# RS485.net
KiCad netlist of a schematic drawn in Altium Designer
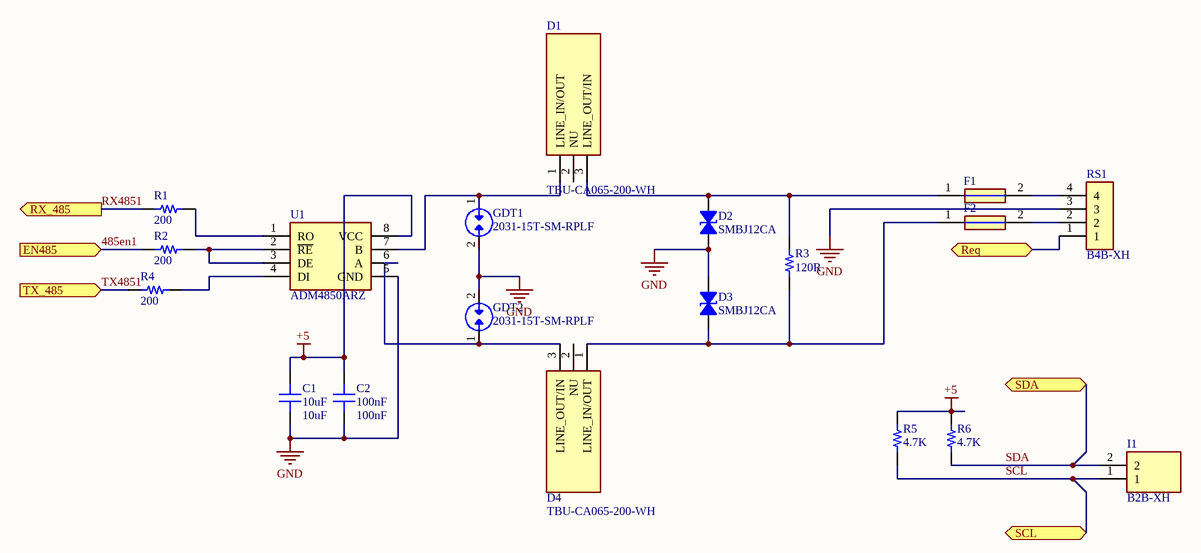
[diagram p0: RS485.SchDoc]

(export (version "E")
  (design (tool "Eeschema 10.0.6"))
  (components
    (comp (ref "C1")
      (value "10uF")
      (footprint "cap805")
      (description "CAP SMD 0805")
      (fields (field (name "PART NUMBER") "C0805X106K9RAC7800") (field (name "ALTIUM_VALUE") "10uF"))
      (libsource (lib "lamp control-ver2") (part "Capacitor"))
    )
    (comp (ref "C2")
      (value "100nF")
      (footprint "cap805")
      (description "CAP SMD 0805")
      (fields (field (name "PART NUMBER") "C0805X106K9RAC7800") (field (name "ALTIUM_VALUE") "100nF"))
      (libsource (lib "lamp control-ver2") (part "Capacitor"))
    )
    (comp (ref "D1")
      (value "TBU-CA065-200-WH")
      (footprint "TBUCA025050WH")
      (description "TVS Diode (Bi-directional)")
      (fields (field (name "MOUSER PART NUMBER") "652-TBU-CA065-200-WH"))
      (libsource (lib "*") (part "TBU-CA065-200-WH"))
    )
    (comp (ref "D2")
      (value "SMBJ12CA")
      (footprint "DO214AA SMB")
      (description "TVS DIODE 12V 19.9V SMB")
      (fields (field (name "MANUFACTURER") "AVX Corporation"))
      (libsource (lib "Celestial Altium Library - altium_library") (part "Diode TVS"))
    )
    (comp (ref "D3")
      (value "SMBJ12CA")
      (footprint "DO214AA SMB")
      (description "TVS DIODE 12V 19.9V SMB")
      (fields (field (name "MANUFACTURER") "AVX Corporation"))
      (libsource (lib "Celestial Altium Library - altium_library") (part "Diode TVS"))
    )
    (comp (ref "D4")
      (value "TBU-CA065-200-WH")
      (footprint "TBUCA025050WH")
      (description "TVS Diode (Bi-directional)")
      (fields (field (name "MOUSER PART NUMBER") "652-TBU-CA065-200-WH"))
      (libsource (lib "") (part "TBU-CA065-200-WH_1"))
    )
    (comp (ref "F1")
      (value "fuse 100mAmp")
      (footprint "fuse3216")
      (description "Fuse 1206")
      (fields (field (name "MANUFACTURER_PART_NUMBER") "1206SFS200F/63-2"))
      (libsource (lib "*") (part "1206SFS200F_63-2"))
    )
    (comp (ref "F2")
      (value "fuse 100mAmp")
      (footprint "fuse3216")
      (description "Fuse 1206")
      (fields (field (name "MANUFACTURER_PART_NUMBER") "1206SFS200F/63-2"))
      (libsource (lib "*") (part "1206SFS200F_63-2"))
    )
    (comp (ref "GDT1")
      (value "2031-15T-SM-RPLF")
      (footprint "TVS_2031-15T-SM-RPLF")
      (description "Gas Discharge Tube SMD")
      (libsource (lib "2031-15T-SM-RPLF") (part "2031-15T-SM-RPLF"))
    )
    (comp (ref "GDT2")
      (value "2031-15T-SM-RPLF")
      (footprint "TVS_2031-15T-SM-RPLF")
      (description "Gas Discharge Tube SMD")
      (libsource (lib "2031-15T-SM-RPLF") (part "2031-15T-SM-RPLF"))
    )
    (comp (ref "I1")
      (value "B2B-XH")
      (footprint "JST-B2B-XH")
      (description "XH 2pin standing")
      (libsource (lib "XHBBLIB") (part "B2B-XH"))
    )
    (comp (ref "R1")
      (value "200")
      (footprint "0603R")
      (description "RES SMD 0603")
      (fields (field (name "PART NUMBER") "CRCW080510K0JNEAIF") (field (name "MANUFACTURER") "Vishay Dale"))
      (libsource (lib "Celestial Altium Library - altium_library") (part "Resistor"))
    )
    (comp (ref "R2")
      (value "200")
      (footprint "0603R")
      (description "RES SMD 0603")
      (fields (field (name "PART NUMBER") "CRCW080510K0JNEAIF") (field (name "MANUFACTURER") "Vishay Dale"))
      (libsource (lib "Celestial Altium Library - altium_library") (part "Resistor"))
    )
    (comp (ref "R3")
      (value "120R")
      (footprint "0603R")
      (description "RES SMD 0603")
      (fields (field (name "PART NUMBER") "CRCW080510K0JNEAIF") (field (name "MANUFACTURER") "Vishay Dale"))
      (libsource (lib "Celestial Altium Library - altium_library") (part "Resistor"))
    )
    (comp (ref "R4")
      (value "200")
      (footprint "0603R")
      (description "RES SMD 0603")
      (fields (field (name "PART NUMBER") "CRCW080510K0JNEAIF") (field (name "MANUFACTURER") "Vishay Dale"))
      (libsource (lib "Celestial Altium Library - altium_library") (part "Resistor"))
    )
    (comp (ref "R5")
      (value "4.7K")
      (footprint "0603R")
      (description "RES SMD 0603")
      (fields (field (name "PART NUMBER") "CRCW080510K0JNEAIF") (field (name "MANUFACTURER") "Vishay Dale"))
      (libsource (lib "Celestial Altium Library - altium_library") (part "Resistor"))
    )
    (comp (ref "R6")
      (value "4.7K")
      (footprint "0603R")
      (description "RES SMD 0603")
      (fields (field (name "PART NUMBER") "CRCW080510K0JNEAIF") (field (name "MANUFACTURER") "Vishay Dale"))
      (libsource (lib "Celestial Altium Library - altium_library") (part "Resistor"))
    )
    (comp (ref "RS1")
      (value "B4B-XH")
      (footprint "JST-B4B-XH")
      (description "XH 4pin standing")
      (libsource (lib "XHBBLIB") (part "B4B-XH"))
    )
    (comp (ref "U1")
      (value "ADM4850ARZ")
      (footprint "SO8_N")
      (description "MAX485 SMD")
      (fields (field (name "MOUSER PART NUMBER") "584-ADM4850ARZ"))
      (libsource (lib "*") (part "ADM4850ARZ"))
    )
  )
  (nets
    (net (code "1") (name "+5") (class "Default")
      (node (ref "C1") (pin "1") (pinfunction "1_1") (pintype "passive"))
      (node (ref "C2") (pin "1") (pinfunction "1_1") (pintype "passive"))
      (node (ref "R5") (pin "1") (pinfunction "1_1") (pintype "passive"))
      (node (ref "R6") (pin "1") (pinfunction "1_1") (pintype "passive"))
      (node (ref "U1") (pin "8") (pinfunction "VCC_8") (pintype "passive"))
    )
    (net (code "2") (name "/485en1") (class "Default")
      (node (ref "R2") (pin "2") (pinfunction "2_2") (pintype "passive"))
    )
    (net (code "3") (name "/RX4851") (class "Default")
      (node (ref "R1") (pin "2") (pinfunction "2_2") (pintype "passive"))
    )
    (net (code "4") (name "/Req") (class "Default")
      (node (ref "RS1") (pin "1") (pinfunction "1_1") (pintype "passive"))
    )
    (net (code "5") (name "/SCL") (class "Default")
      (node (ref "I1") (pin "1") (pinfunction "1_1") (pintype "passive"))
      (node (ref "R5") (pin "2") (pinfunction "2_2") (pintype "passive"))
    )
    (net (code "6") (name "/SDA") (class "Default")
      (node (ref "I1") (pin "2") (pinfunction "2_2") (pintype "passive"))
      (node (ref "R6") (pin "2") (pinfunction "2_2") (pintype "passive"))
    )
    (net (code "7") (name "/TX4851") (class "Default")
      (node (ref "R4") (pin "2") (pinfunction "2_2") (pintype "passive"))
    )
    (net (code "8") (name "GND") (class "Default")
      (node (ref "C1") (pin "2") (pinfunction "2_2") (pintype "passive"))
      (node (ref "C2") (pin "2") (pinfunction "2_2") (pintype "passive"))
      (node (ref "D2") (pin "1") (pinfunction "1_1") (pintype "passive"))
      (node (ref "D3") (pin "2") (pinfunction "2_2") (pintype "passive"))
      (node (ref "GDT1") (pin "2") (pinfunction "2_2") (pintype "passive"))
      (node (ref "GDT2") (pin "2") (pinfunction "2_2") (pintype "passive"))
      (node (ref "RS1") (pin "3") (pinfunction "3_3") (pintype "passive"))
      (node (ref "U1") (pin "5") (pinfunction "GND_5") (pintype "passive"))
    )
    (net (code "9") (name "Net-(D1-LINE_IN{slash}OUT)") (class "Default")
      (node (ref "D1") (pin "1") (pinfunction "LINE_IN/OUT_1") (pintype "passive"))
      (node (ref "GDT1") (pin "1") (pinfunction "1_1") (pintype "passive"))
      (node (ref "U1") (pin "7") (pinfunction "B_7") (pintype "passive"))
    )
    (net (code "10") (name "Net-(D1-LINE_OUT{slash}IN)") (class "Default")
      (node (ref "D1") (pin "3") (pinfunction "LINE_OUT/IN_3") (pintype "passive"))
      (node (ref "D2") (pin "2") (pinfunction "2_2") (pintype "passive"))
      (node (ref "F1") (pin "1") (pinfunction "1_1") (pintype "passive"))
      (node (ref "R3") (pin "1") (pinfunction "1_1") (pintype "passive"))
    )
    (net (code "11") (name "Net-(D4-LINE_IN{slash}OUT)") (class "Default")
      (node (ref "D3") (pin "1") (pinfunction "1_1") (pintype "passive"))
      (node (ref "D4") (pin "1") (pinfunction "LINE_IN/OUT_1") (pintype "passive"))
      (node (ref "F2") (pin "1") (pinfunction "1_1") (pintype "passive"))
      (node (ref "R3") (pin "2") (pinfunction "2_2") (pintype "passive"))
    )
    (net (code "12") (name "Net-(D4-LINE_OUT{slash}IN)") (class "Default")
      (node (ref "D4") (pin "3") (pinfunction "LINE_OUT/IN_3") (pintype "passive"))
      (node (ref "GDT2") (pin "1") (pinfunction "1_1") (pintype "passive"))
      (node (ref "U1") (pin "6") (pinfunction "A_6") (pintype "passive"))
    )
    (net (code "13") (name "Net-(F1-Pad2)") (class "Default")
      (node (ref "F1") (pin "2") (pinfunction "2_2") (pintype "passive"))
      (node (ref "RS1") (pin "4") (pinfunction "4_4") (pintype "passive"))
    )
    (net (code "14") (name "Net-(F2-Pad2)") (class "Default")
      (node (ref "F2") (pin "2") (pinfunction "2_2") (pintype "passive"))
      (node (ref "RS1") (pin "2") (pinfunction "2_2") (pintype "passive"))
    )
    (net (code "15") (name "Net-(U1-DE)") (class "Default")
      (node (ref "R2") (pin "1") (pinfunction "1_1") (pintype "passive"))
      (node (ref "U1") (pin "2") (pinfunction "~{RE}_2") (pintype "passive"))
      (node (ref "U1") (pin "3") (pinfunction "DE_3") (pintype "passive"))
    )
    (net (code "16") (name "Net-(U1-DI)") (class "Default")
      (node (ref "R4") (pin "1") (pinfunction "1_1") (pintype "passive"))
      (node (ref "U1") (pin "4") (pinfunction "DI_4") (pintype "passive"))
    )
    (net (code "17") (name "Net-(U1-RO)") (class "Default")
      (node (ref "R1") (pin "1") (pinfunction "1_1") (pintype "passive"))
      (node (ref "U1") (pin "1") (pinfunction "RO_1") (pintype "passive"))
    )
    (net (code "18") (name "unconnected-(D1-NU-Pad2)") (class "Default")
      (node (ref "D1") (pin "2") (pinfunction "NU_2") (pintype "passive"))
    )
    (net (code "19") (name "unconnected-(D4-NU-Pad2)") (class "Default")
      (node (ref "D4") (pin "2") (pinfunction "NU_2") (pintype "passive"))
    )
  )
)
